# LED_Driver.net
KiCad netlist of a schematic drawn in Altium Designer
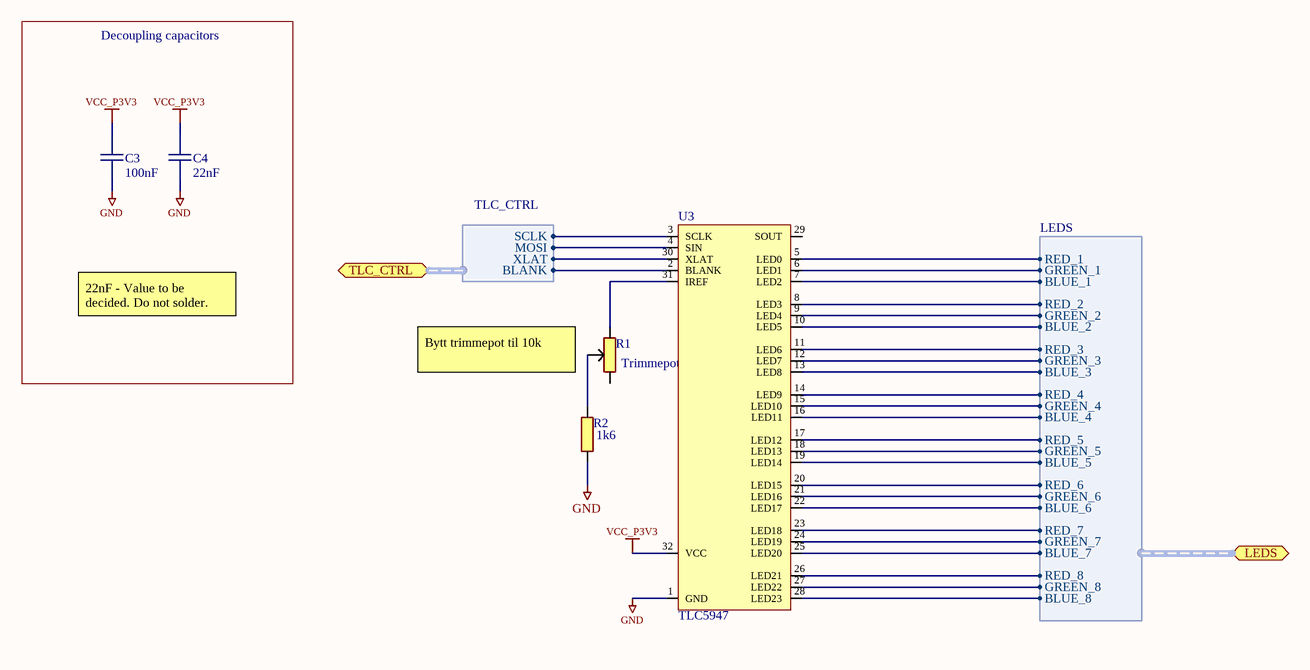
[diagram p0: LED Driver.SchDoc]

(export (version "E")
  (design (tool "Eeschema 10.0.6"))
  (components
    (comp (ref "C3")
      (value "100nF")
      (footprint "CAPC0603(1608)55_N")
      (description "X7R 50V 5%")
      (libsource (lib "OVLib") (part "CAP"))
    )
    (comp (ref "C4")
      (value "22nF")
      (footprint "CAPC0805(2012)100_N")
      (description "X7R 50V")
      (libsource (lib "OVLib") (part "CAP"))
    )
    (comp (ref "R1")
      (value "Trimmepot 500ohm")
      (footprint "TRIMPOT_3006P")
      (description "15 turn, horizontal")
      (libsource (lib "OVLib") (part "Potmeter"))
    )
    (comp (ref "R2")
      (value "1k6")
      (footprint "RESC0603(1608)_N")
      (description "0.1W 1% Thick film resistor")
      (libsource (lib "OVLib") (part "Resistor2"))
    )
    (comp (ref "U3") (value "TLC5947") (footprint "TLC5947") (libsource (lib "Schlib1") (part "TLC5947")))
  )
  (nets
    (net (code "3") (name "/BLANK") (class "Default")
      (node (ref "U3") (pin "2") (pinfunction "BLANK_2") (pintype "passive"))
    )
    (net (code "4") (name "/BLUE_1") (class "Default")
      (node (ref "U3") (pin "7") (pinfunction "LED2_7") (pintype "passive"))
    )
    (net (code "5") (name "/BLUE_2") (class "Default")
      (node (ref "U3") (pin "10") (pinfunction "LED5_10") (pintype "passive"))
    )
    (net (code "6") (name "/BLUE_3") (class "Default")
      (node (ref "U3") (pin "13") (pinfunction "LED8_13") (pintype "passive"))
    )
    (net (code "7") (name "/BLUE_4") (class "Default")
      (node (ref "U3") (pin "16") (pinfunction "LED11_16") (pintype "passive"))
    )
    (net (code "8") (name "/BLUE_5") (class "Default")
      (node (ref "U3") (pin "19") (pinfunction "LED14_19") (pintype "passive"))
    )
    (net (code "9") (name "/BLUE_6") (class "Default")
      (node (ref "U3") (pin "22") (pinfunction "LED17_22") (pintype "passive"))
    )
    (net (code "10") (name "/BLUE_7") (class "Default")
      (node (ref "U3") (pin "25") (pinfunction "LED20_25") (pintype "passive"))
    )
    (net (code "11") (name "/BLUE_8") (class "Default")
      (node (ref "U3") (pin "28") (pinfunction "LED23_28") (pintype "passive"))
    )
    (net (code "12") (name "/GREEN_1") (class "Default")
      (node (ref "U3") (pin "6") (pinfunction "LED1_6") (pintype "passive"))
    )
    (net (code "13") (name "/GREEN_2") (class "Default")
      (node (ref "U3") (pin "9") (pinfunction "LED4_9") (pintype "passive"))
    )
    (net (code "14") (name "/GREEN_3") (class "Default")
      (node (ref "U3") (pin "12") (pinfunction "LED7_12") (pintype "passive"))
    )
    (net (code "15") (name "/GREEN_4") (class "Default")
      (node (ref "U3") (pin "15") (pinfunction "LED10_15") (pintype "passive"))
    )
    (net (code "16") (name "/GREEN_5") (class "Default")
      (node (ref "U3") (pin "18") (pinfunction "LED13_18") (pintype "passive"))
    )
    (net (code "17") (name "/GREEN_6") (class "Default")
      (node (ref "U3") (pin "21") (pinfunction "LED16_21") (pintype "passive"))
    )
    (net (code "18") (name "/GREEN_7") (class "Default")
      (node (ref "U3") (pin "24") (pinfunction "LED19_24") (pintype "passive"))
    )
    (net (code "19") (name "/GREEN_8") (class "Default")
      (node (ref "U3") (pin "27") (pinfunction "LED22_27") (pintype "passive"))
    )
    (net (code "20") (name "/MOSI") (class "Default")
      (node (ref "U3") (pin "4") (pinfunction "SIN_4") (pintype "passive"))
    )
    (net (code "21") (name "/RED_1") (class "Default")
      (node (ref "U3") (pin "5") (pinfunction "LED0_5") (pintype "passive"))
    )
    (net (code "22") (name "/RED_2") (class "Default")
      (node (ref "U3") (pin "8") (pinfunction "LED3_8") (pintype "passive"))
    )
    (net (code "23") (name "/RED_3") (class "Default")
      (node (ref "U3") (pin "11") (pinfunction "LED6_11") (pintype "passive"))
    )
    (net (code "24") (name "/RED_4") (class "Default")
      (node (ref "U3") (pin "14") (pinfunction "LED9_14") (pintype "passive"))
    )
    (net (code "25") (name "/RED_5") (class "Default")
      (node (ref "U3") (pin "17") (pinfunction "LED12_17") (pintype "passive"))
    )
    (net (code "26") (name "/RED_6") (class "Default")
      (node (ref "U3") (pin "20") (pinfunction "LED15_20") (pintype "passive"))
    )
    (net (code "27") (name "/RED_7") (class "Default")
      (node (ref "U3") (pin "23") (pinfunction "LED18_23") (pintype "passive"))
    )
    (net (code "28") (name "/RED_8") (class "Default")
      (node (ref "U3") (pin "26") (pinfunction "LED21_26") (pintype "passive"))
    )
    (net (code "29") (name "/SCLK") (class "Default")
      (node (ref "U3") (pin "3") (pinfunction "SCLK_3") (pintype "passive"))
    )
    (net (code "30") (name "/XLAT") (class "Default")
      (node (ref "U3") (pin "30") (pinfunction "XLAT_30") (pintype "passive"))
    )
    (net (code "33") (name "GND") (class "Default")
      (node (ref "C3") (pin "1") (pinfunction "1_1") (pintype "passive"))
      (node (ref "C4") (pin "1") (pinfunction "1_1") (pintype "passive"))
      (node (ref "R2") (pin "1") (pinfunction "1_1") (pintype "passive"))
      (node (ref "U3") (pin "1") (pinfunction "GND_1") (pintype "passive"))
    )
    (net (code "34") (name "Net-(R1-Pad2)") (class "Default")
      (node (ref "R1") (pin "2") (pinfunction "2_2") (pintype "passive"))
      (node (ref "R2") (pin "2") (pinfunction "2_2") (pintype "passive"))
    )
    (net (code "35") (name "Net-(U3-IREF)") (class "Default")
      (node (ref "R1") (pin "3") (pinfunction "3_3") (pintype "passive"))
      (node (ref "U3") (pin "31") (pinfunction "IREF_31") (pintype "passive"))
    )
    (net (code "36") (name "VCC_P3V3") (class "Default")
      (node (ref "C3") (pin "2") (pinfunction "2_2") (pintype "passive"))
      (node (ref "C4") (pin "2") (pinfunction "2_2") (pintype "passive"))
      (node (ref "U3") (pin "32") (pinfunction "VCC_32") (pintype "passive"))
    )
    (net (code "37") (name "unconnected-(R1-Pad1)") (class "Default")
      (node (ref "R1") (pin "1") (pinfunction "1_1") (pintype "passive"))
    )
    (net (code "38") (name "unconnected-(U3-SOUT-Pad29)") (class "Default")
      (node (ref "U3") (pin "29") (pinfunction "SOUT_29") (pintype "passive"))
    )
  )
)
